# SCH_Curtain_PCB_2022-04-27.net
KiCad netlist of a schematic drawn in EasyEDA
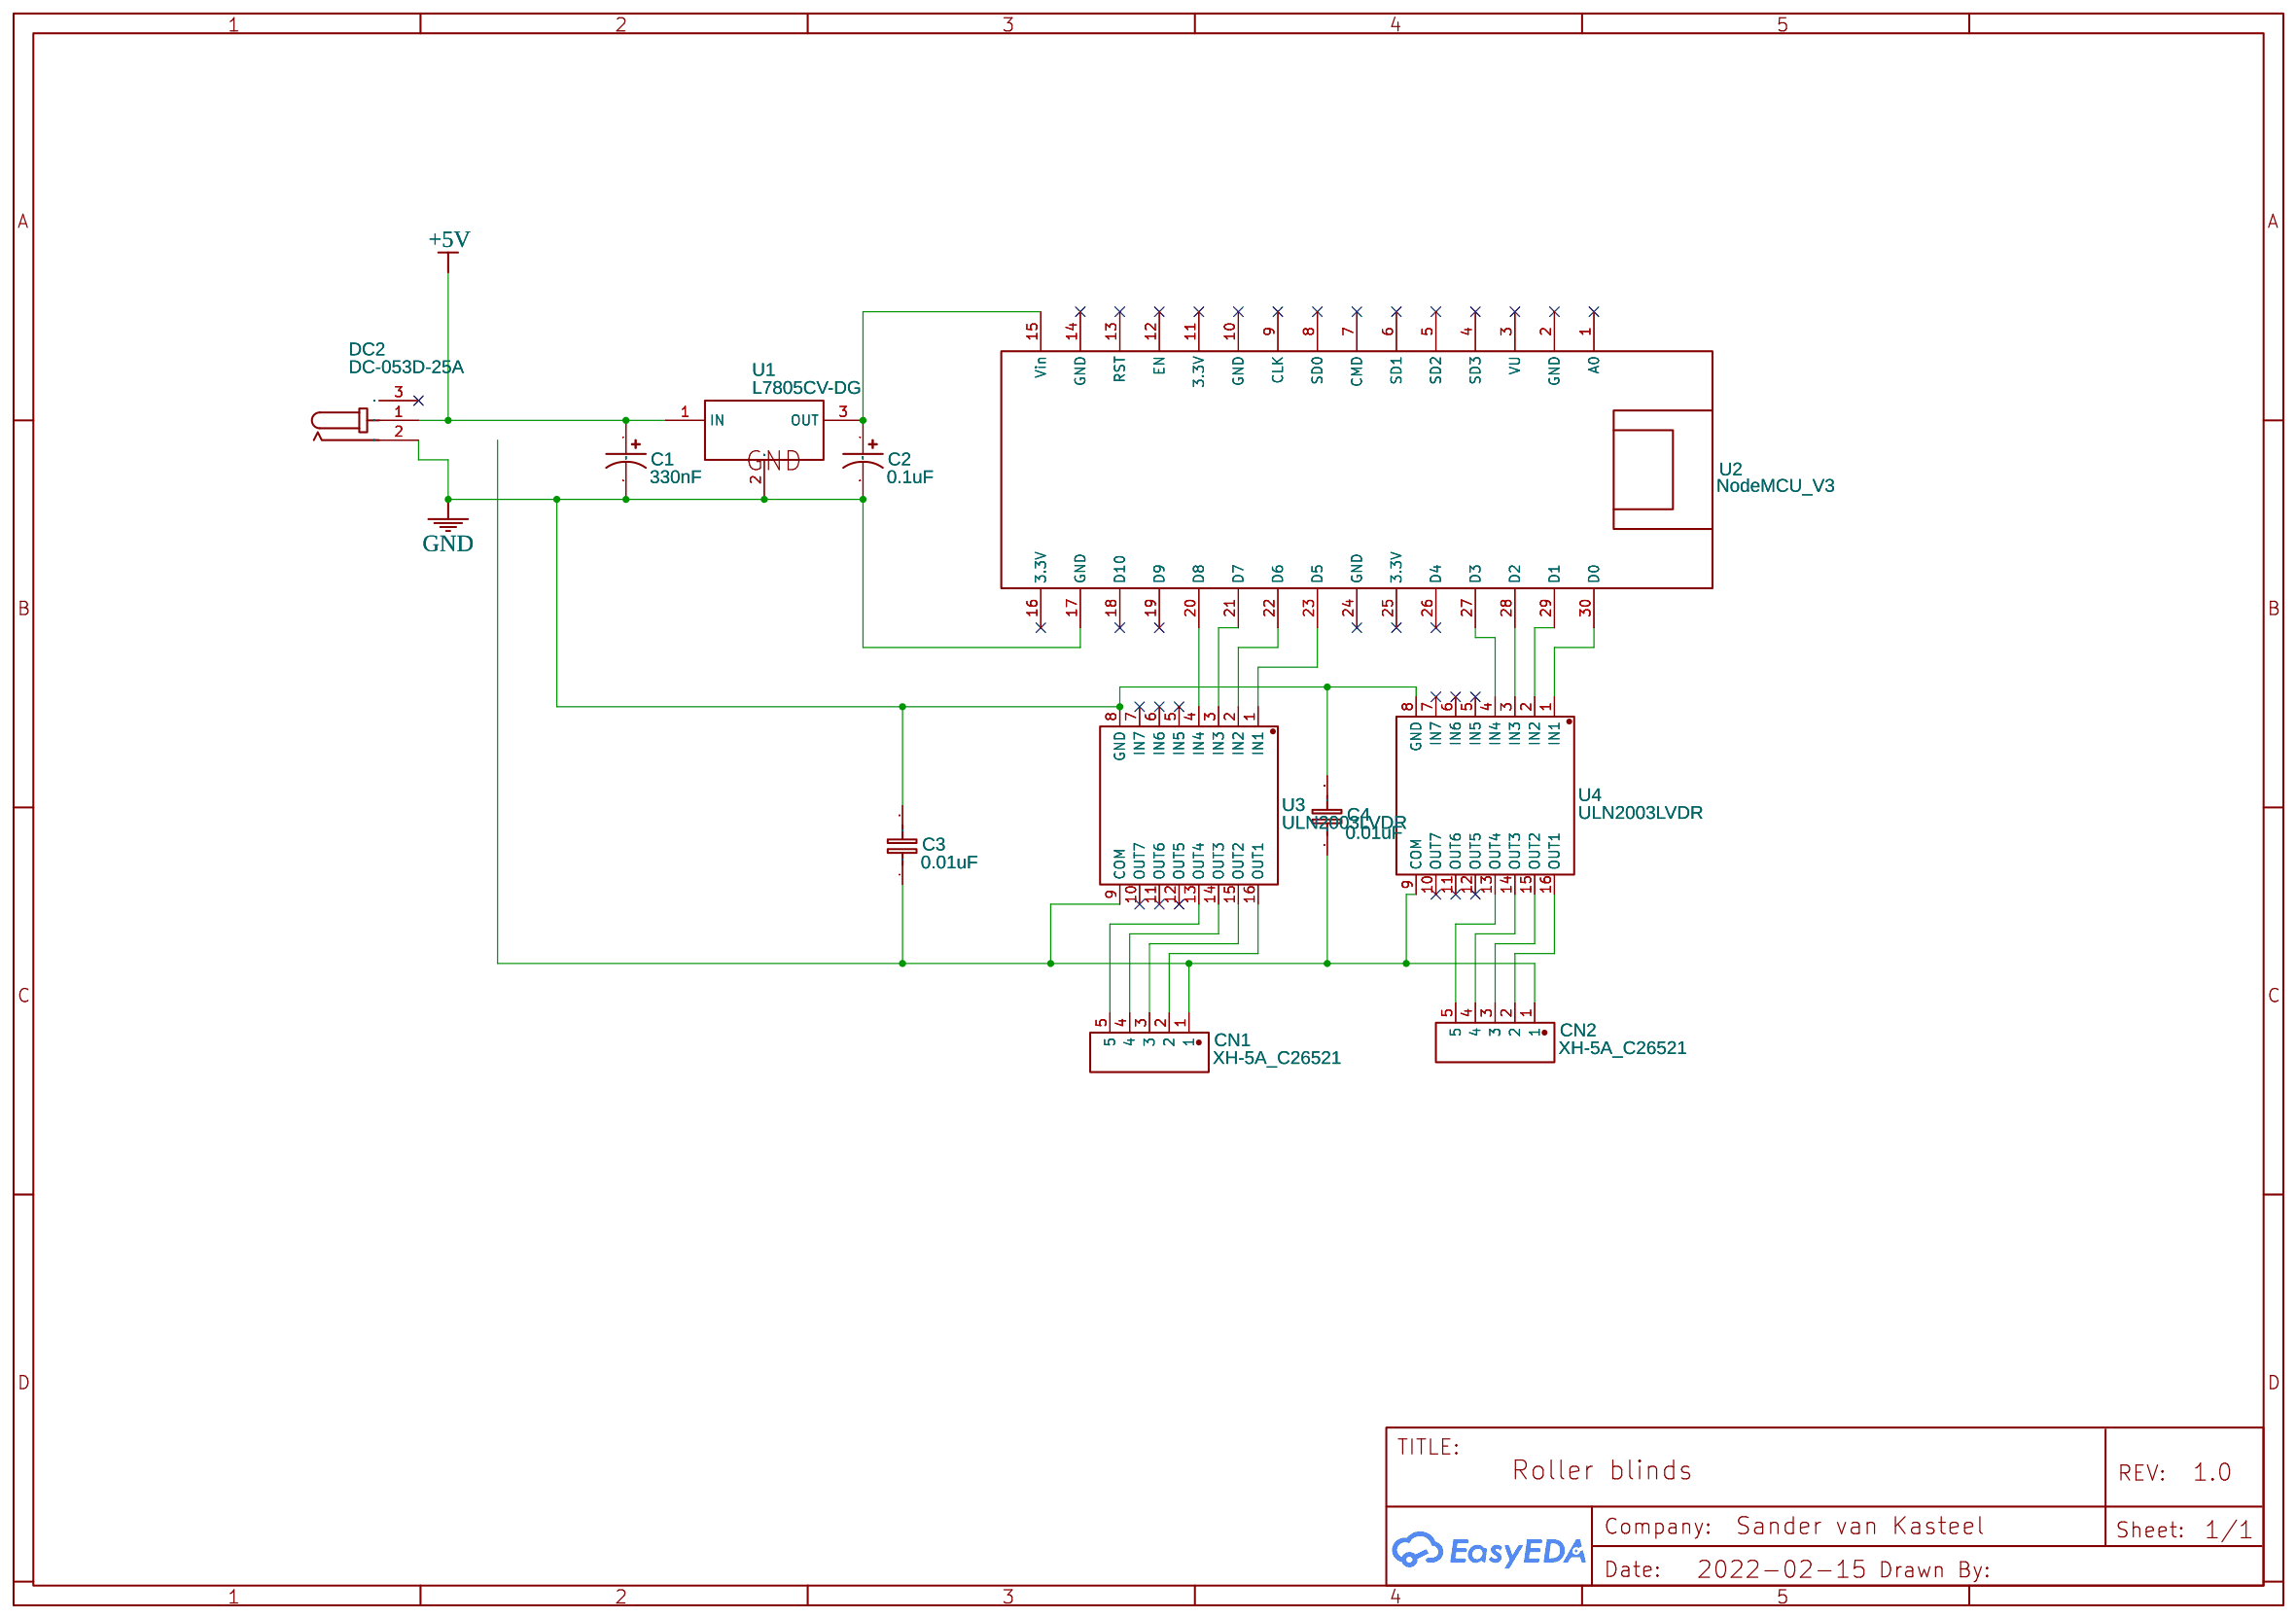
[diagram p0: schematic sheet]

(export (version "E")
  (design (tool "Eeschema 10.0.6"))
  (components
    (comp (ref "C1")
      (value "330nF")
      (fields
        (field (name "BOM_Manufacturer Part") "CL21B334KBFNNNE")
        (field (name "BOM_Supplier Part") "C73142")
      )
      (libsource (lib "") (part "C_Tan_SMD_A_US"))
    )
    (comp (ref "C2")
      (value "0.1uF")
      (fields
        (field (name "BOM_Manufacturer Part") "CT41G-0805-2X1-50V-0.1uF-K(N)")
        (field (name "BOM_Supplier Part") "C126469")
      )
      (libsource (lib "") (part "C_Tan_SMD_A_US"))
    )
    (comp (ref "C3")
      (value "0.01uF")
      (fields
        (field (name "BOM_Manufacturer Part") "CT41-0603-2X1-50V-0.01uF-K(N)")
        (field (name "BOM_Supplier Part") "C138345")
      )
      (libsource (lib "") (part "C_0603_EU_1"))
    )
    (comp (ref "C4")
      (value "0.01uF")
      (fields
        (field (name "BOM_Manufacturer Part") "CT41-0603-2X1-50V-0.01uF-K(N)")
        (field (name "BOM_Supplier Part") "C138345")
      )
      (libsource (lib "") (part "C_0603_EU"))
    )
    (comp (ref "CN1")
      (value "XH-5A_C26521")
      (fields (field (name "BOM_Manufacturer Part") "XH-5A") (field (name "BOM_Supplier Part") "C26521"))
      (libsource (lib "") (part "XH-5A_C26521"))
    )
    (comp (ref "CN2")
      (value "XH-5A_C26521")
      (fields (field (name "BOM_Manufacturer Part") "XH-5A") (field (name "BOM_Supplier Part") "C26521"))
      (libsource (lib "") (part "XH-5A_C26521"))
    )
    (comp (ref "DC2")
      (value "DC-053D-25A")
      (fields (field (name "BOM_Supplier Part") "C2686352"))
      (libsource (lib "") (part "DC-053D-25A"))
    )
    (comp (ref "U1")
      (value "L7805CV-DG")
      (fields (field (name "BOM_Supplier Part") "C3795"))
      (libsource (lib "") (part "L7805CV-DG"))
    )
    (comp (ref "U2") (value "NodeMCU_V3") (libsource (lib "") (part "NodeMCU_V3")))
    (comp (ref "U3")
      (value "ULN2003LVDR")
      (fields (field (name "BOM_Supplier Part") "C72751"))
      (libsource (lib "") (part "ULN2003LVDR"))
    )
    (comp (ref "U4")
      (value "ULN2003LVDR")
      (fields (field (name "BOM_Supplier Part") "C72751"))
      (libsource (lib "") (part "ULN2003LVDR"))
    )
  )
  (nets
    (net (code "1") (name "+5V") (class "Default")
      (node (ref "C1") (pin "1") (pinfunction "1_1") (pintype "unspecified"))
      (node (ref "DC2") (pin "1") (pinfunction "1_1") (pintype "unspecified"))
      (node (ref "U1") (pin "1") (pinfunction "IN_1") (pintype "passive"))
    )
    (net (code "2") (name "GND") (class "Default")
      (node (ref "C1") (pin "2") (pinfunction "2_2") (pintype "unspecified"))
      (node (ref "C2") (pin "2") (pinfunction "2_2") (pintype "unspecified"))
      (node (ref "C3") (pin "2") (pinfunction "2_2") (pintype "unspecified"))
      (node (ref "C4") (pin "2") (pinfunction "2_2") (pintype "unspecified"))
      (node (ref "DC2") (pin "2") (pinfunction "2_2") (pintype "unspecified"))
      (node (ref "U1") (pin "2") (pinfunction "GND_2") (pintype "passive"))
      (node (ref "U2") (pin "17") (pinfunction "GND_17") (pintype "unspecified"))
      (node (ref "U3") (pin "8") (pinfunction "GND_8") (pintype "unspecified"))
      (node (ref "U4") (pin "8") (pinfunction "GND_8") (pintype "unspecified"))
    )
    (net (code "3") (name "Net-(U1-OUT)") (class "Default")
      (node (ref "C2") (pin "1") (pinfunction "1_1") (pintype "unspecified"))
      (node (ref "U1") (pin "3") (pinfunction "OUT_3") (pintype "passive"))
      (node (ref "U2") (pin "15") (pinfunction "Vin_15") (pintype "unspecified"))
    )
    (net (code "4") (name "Net-(U2-D0)") (class "Default")
      (node (ref "U2") (pin "30") (pinfunction "D0_30") (pintype "unspecified"))
      (node (ref "U4") (pin "1") (pinfunction "IN1_1") (pintype "unspecified"))
    )
    (net (code "5") (name "Net-(U2-D1)") (class "Default")
      (node (ref "U2") (pin "29") (pinfunction "D1_29") (pintype "unspecified"))
      (node (ref "U4") (pin "2") (pinfunction "IN2_2") (pintype "unspecified"))
    )
    (net (code "6") (name "Net-(U2-D2)") (class "Default")
      (node (ref "U2") (pin "28") (pinfunction "D2_28") (pintype "unspecified"))
      (node (ref "U4") (pin "3") (pinfunction "IN3_3") (pintype "unspecified"))
    )
    (net (code "7") (name "Net-(U2-D3)") (class "Default")
      (node (ref "U2") (pin "27") (pinfunction "D3_27") (pintype "unspecified"))
      (node (ref "U4") (pin "4") (pinfunction "IN4_4") (pintype "unspecified"))
    )
    (net (code "8") (name "Net-(U2-D5)") (class "Default")
      (node (ref "U2") (pin "23") (pinfunction "D5_23") (pintype "unspecified"))
      (node (ref "U3") (pin "1") (pinfunction "IN1_1") (pintype "unspecified"))
    )
    (net (code "9") (name "Net-(U2-D6)") (class "Default")
      (node (ref "U2") (pin "22") (pinfunction "D6_22") (pintype "unspecified"))
      (node (ref "U3") (pin "2") (pinfunction "IN2_2") (pintype "unspecified"))
    )
    (net (code "10") (name "Net-(U2-D7)") (class "Default")
      (node (ref "U2") (pin "21") (pinfunction "D7_21") (pintype "unspecified"))
      (node (ref "U3") (pin "3") (pinfunction "IN3_3") (pintype "unspecified"))
    )
    (net (code "11") (name "Net-(U2-D8)") (class "Default")
      (node (ref "U2") (pin "20") (pinfunction "D8_20") (pintype "unspecified"))
      (node (ref "U3") (pin "4") (pinfunction "IN4_4") (pintype "unspecified"))
    )
    (net (code "12") (name "Net-(U3-COM)") (class "Default")
      (node (ref "C3") (pin "1") (pinfunction "1_1") (pintype "unspecified"))
      (node (ref "C4") (pin "1") (pinfunction "1_1") (pintype "unspecified"))
      (node (ref "CN1") (pin "1") (pinfunction "1_1") (pintype "unspecified"))
      (node (ref "CN2") (pin "1") (pinfunction "1_1") (pintype "unspecified"))
      (node (ref "U3") (pin "9") (pinfunction "COM_9") (pintype "unspecified"))
      (node (ref "U4") (pin "9") (pinfunction "COM_9") (pintype "unspecified"))
    )
    (net (code "13") (name "Net-(U3-OUT1)") (class "Default")
      (node (ref "CN1") (pin "2") (pinfunction "2_2") (pintype "unspecified"))
      (node (ref "U3") (pin "16") (pinfunction "OUT1_16") (pintype "unspecified"))
    )
    (net (code "14") (name "Net-(U3-OUT2)") (class "Default")
      (node (ref "CN1") (pin "3") (pinfunction "3_3") (pintype "unspecified"))
      (node (ref "U3") (pin "15") (pinfunction "OUT2_15") (pintype "unspecified"))
    )
    (net (code "15") (name "Net-(U3-OUT3)") (class "Default")
      (node (ref "CN1") (pin "4") (pinfunction "4_4") (pintype "unspecified"))
      (node (ref "U3") (pin "14") (pinfunction "OUT3_14") (pintype "unspecified"))
    )
    (net (code "16") (name "Net-(U3-OUT4)") (class "Default")
      (node (ref "CN1") (pin "5") (pinfunction "5_5") (pintype "unspecified"))
      (node (ref "U3") (pin "13") (pinfunction "OUT4_13") (pintype "unspecified"))
    )
    (net (code "17") (name "Net-(U4-OUT1)") (class "Default")
      (node (ref "CN2") (pin "2") (pinfunction "2_2") (pintype "unspecified"))
      (node (ref "U4") (pin "16") (pinfunction "OUT1_16") (pintype "unspecified"))
    )
    (net (code "18") (name "Net-(U4-OUT2)") (class "Default")
      (node (ref "CN2") (pin "3") (pinfunction "3_3") (pintype "unspecified"))
      (node (ref "U4") (pin "15") (pinfunction "OUT2_15") (pintype "unspecified"))
    )
    (net (code "19") (name "Net-(U4-OUT3)") (class "Default")
      (node (ref "CN2") (pin "4") (pinfunction "4_4") (pintype "unspecified"))
      (node (ref "U4") (pin "14") (pinfunction "OUT3_14") (pintype "unspecified"))
    )
    (net (code "20") (name "Net-(U4-OUT4)") (class "Default")
      (node (ref "CN2") (pin "5") (pinfunction "5_5") (pintype "unspecified"))
      (node (ref "U4") (pin "13") (pinfunction "OUT4_13") (pintype "unspecified"))
    )
    (net (code "21") (name "unconnected-(DC2-Pad3)") (class "Default")
      (node (ref "DC2") (pin "3") (pinfunction "3_3") (pintype "unspecified+no_connect"))
    )
    (net (code "22") (name "unconnected-(U2-3.3V-Pad11)") (class "Default")
      (node (ref "U2") (pin "11") (pinfunction "3.3V_11") (pintype "unspecified+no_connect"))
    )
    (net (code "23") (name "unconnected-(U2-3.3V-Pad16)") (class "Default")
      (node (ref "U2") (pin "16") (pinfunction "3.3V_16") (pintype "unspecified+no_connect"))
    )
    (net (code "24") (name "unconnected-(U2-3.3V-Pad25)") (class "Default")
      (node (ref "U2") (pin "25") (pinfunction "3.3V_25") (pintype "unspecified+no_connect"))
    )
    (net (code "25") (name "unconnected-(U2-A0-Pad1)") (class "Default")
      (node (ref "U2") (pin "1") (pinfunction "A0_1") (pintype "unspecified+no_connect"))
    )
    (net (code "26") (name "unconnected-(U2-CLK-Pad9)") (class "Default")
      (node (ref "U2") (pin "9") (pinfunction "CLK_9") (pintype "unspecified+no_connect"))
    )
    (net (code "27") (name "unconnected-(U2-CMD-Pad7)") (class "Default")
      (node (ref "U2") (pin "7") (pinfunction "CMD_7") (pintype "unspecified+no_connect"))
    )
    (net (code "28") (name "unconnected-(U2-D4-Pad26)") (class "Default")
      (node (ref "U2") (pin "26") (pinfunction "D4_26") (pintype "unspecified+no_connect"))
    )
    (net (code "29") (name "unconnected-(U2-D9-Pad19)") (class "Default")
      (node (ref "U2") (pin "19") (pinfunction "D9_19") (pintype "unspecified+no_connect"))
    )
    (net (code "30") (name "unconnected-(U2-D10-Pad18)") (class "Default")
      (node (ref "U2") (pin "18") (pinfunction "D10_18") (pintype "unspecified+no_connect"))
    )
    (net (code "31") (name "unconnected-(U2-EN-Pad12)") (class "Default")
      (node (ref "U2") (pin "12") (pinfunction "EN_12") (pintype "unspecified+no_connect"))
    )
    (net (code "32") (name "unconnected-(U2-GND-Pad2)") (class "Default")
      (node (ref "U2") (pin "2") (pinfunction "GND_2") (pintype "unspecified+no_connect"))
    )
    (net (code "33") (name "unconnected-(U2-GND-Pad10)") (class "Default")
      (node (ref "U2") (pin "10") (pinfunction "GND_10") (pintype "unspecified+no_connect"))
    )
    (net (code "34") (name "unconnected-(U2-GND-Pad14)") (class "Default")
      (node (ref "U2") (pin "14") (pinfunction "GND_14") (pintype "unspecified+no_connect"))
    )
    (net (code "35") (name "unconnected-(U2-GND-Pad24)") (class "Default")
      (node (ref "U2") (pin "24") (pinfunction "GND_24") (pintype "unspecified+no_connect"))
    )
    (net (code "36") (name "unconnected-(U2-RST-Pad13)") (class "Default")
      (node (ref "U2") (pin "13") (pinfunction "RST_13") (pintype "unspecified+no_connect"))
    )
    (net (code "37") (name "unconnected-(U2-SD0-Pad8)") (class "Default")
      (node (ref "U2") (pin "8") (pinfunction "SD0_8") (pintype "unspecified+no_connect"))
    )
    (net (code "38") (name "unconnected-(U2-SD1-Pad6)") (class "Default")
      (node (ref "U2") (pin "6") (pinfunction "SD1_6") (pintype "unspecified+no_connect"))
    )
    (net (code "39") (name "unconnected-(U2-SD2-Pad5)") (class "Default")
      (node (ref "U2") (pin "5") (pinfunction "SD2_5") (pintype "unspecified+no_connect"))
    )
    (net (code "40") (name "unconnected-(U2-SD3-Pad4)") (class "Default")
      (node (ref "U2") (pin "4") (pinfunction "SD3_4") (pintype "unspecified+no_connect"))
    )
    (net (code "41") (name "unconnected-(U2-VU-Pad3)") (class "Default")
      (node (ref "U2") (pin "3") (pinfunction "VU_3") (pintype "unspecified+no_connect"))
    )
    (net (code "42") (name "unconnected-(U3-IN5-Pad5)") (class "Default")
      (node (ref "U3") (pin "5") (pinfunction "IN5_5") (pintype "unspecified+no_connect"))
    )
    (net (code "43") (name "unconnected-(U3-IN6-Pad6)") (class "Default")
      (node (ref "U3") (pin "6") (pinfunction "IN6_6") (pintype "unspecified+no_connect"))
    )
    (net (code "44") (name "unconnected-(U3-IN7-Pad7)") (class "Default")
      (node (ref "U3") (pin "7") (pinfunction "IN7_7") (pintype "unspecified+no_connect"))
    )
    (net (code "45") (name "unconnected-(U3-OUT5-Pad12)") (class "Default")
      (node (ref "U3") (pin "12") (pinfunction "OUT5_12") (pintype "unspecified+no_connect"))
    )
    (net (code "46") (name "unconnected-(U3-OUT6-Pad11)") (class "Default")
      (node (ref "U3") (pin "11") (pinfunction "OUT6_11") (pintype "unspecified+no_connect"))
    )
    (net (code "47") (name "unconnected-(U3-OUT7-Pad10)") (class "Default")
      (node (ref "U3") (pin "10") (pinfunction "OUT7_10") (pintype "unspecified+no_connect"))
    )
    (net (code "48") (name "unconnected-(U4-IN5-Pad5)") (class "Default")
      (node (ref "U4") (pin "5") (pinfunction "IN5_5") (pintype "unspecified+no_connect"))
    )
    (net (code "49") (name "unconnected-(U4-IN6-Pad6)") (class "Default")
      (node (ref "U4") (pin "6") (pinfunction "IN6_6") (pintype "unspecified+no_connect"))
    )
    (net (code "50") (name "unconnected-(U4-IN7-Pad7)") (class "Default")
      (node (ref "U4") (pin "7") (pinfunction "IN7_7") (pintype "unspecified+no_connect"))
    )
    (net (code "51") (name "unconnected-(U4-OUT5-Pad12)") (class "Default")
      (node (ref "U4") (pin "12") (pinfunction "OUT5_12") (pintype "unspecified+no_connect"))
    )
    (net (code "52") (name "unconnected-(U4-OUT6-Pad11)") (class "Default")
      (node (ref "U4") (pin "11") (pinfunction "OUT6_11") (pintype "unspecified+no_connect"))
    )
    (net (code "53") (name "unconnected-(U4-OUT7-Pad10)") (class "Default")
      (node (ref "U4") (pin "10") (pinfunction "OUT7_10") (pintype "unspecified+no_connect"))
    )
  )
)
